# Screen_PCB_250214.net
KiCad netlist of a schematic drawn in Altium Designer
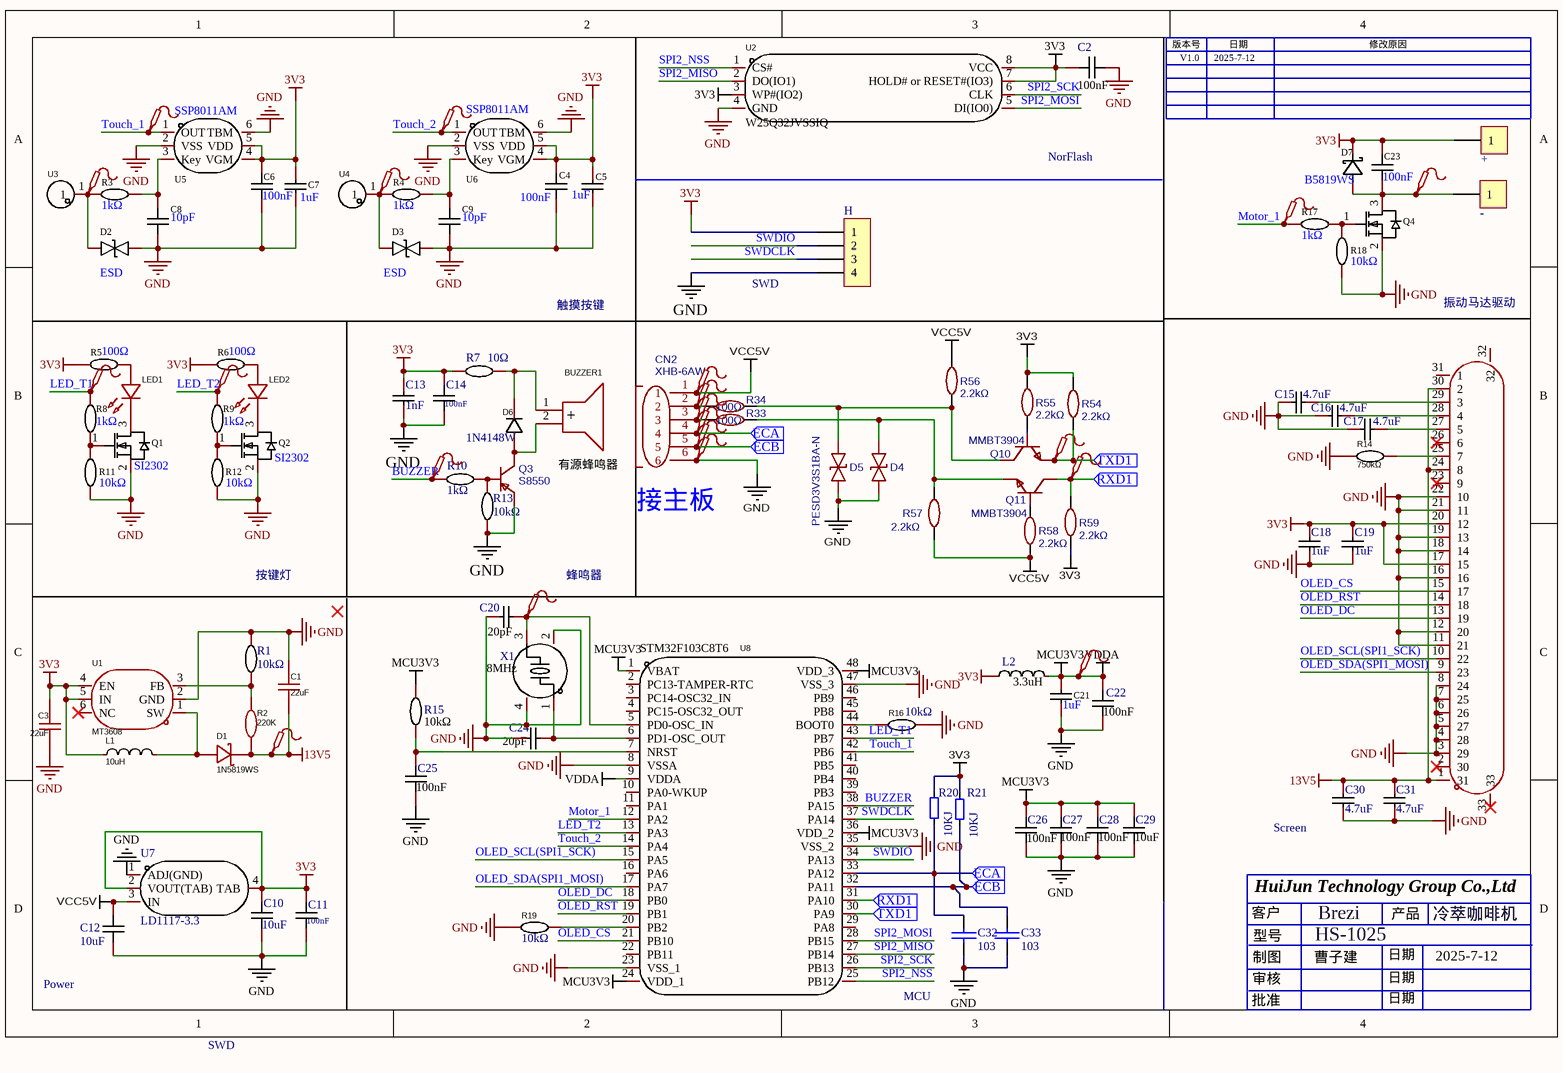
[diagram p0: Screen_PCB_250214.SchDoc]

(export (version "E")
  (design (tool "Eeschema 10.0.6"))
  (components
    (comp (ref "BUZZER1")
      (value "3kHz")
      (footprint "BUZ-TH_BD9.0-P5.00-D0.6-FD")
      (fields (field (name "MANUFACTURER") "华能") (field (name "MANUFACTURER PART") "HNB09A03"))
      (libsource (lib "PCB_Project") (part "HNB09A03"))
    )
    (comp (ref "C1")
      (value "22uF")
      (footprint "C0603")
      (fields
        (field (name "MANUFACTURER") "Chinocera(华瓷)")
        (field (name "MANUFACTURER PART") "HGC0603R5226M100NTHJ")
        (field (name "TOLERANCE") "±20%")
      )
      (libsource (lib "PCB_Project") (part "HGC0603R5226M100NTHJ"))
    )
    (comp (ref "C2")
      (value "CL10B104KB8NNNC")
      (footprint "C0603")
      (fields (field (name "SYMBOL") "100nF") (field (name "MANUFACTURER") "SAMSUNG(三星)"))
      (libsource (lib "altium-import") (part "root_2_CL10B104KB8NNNC_"))
    )
    (comp (ref "C3")
      (value "22uF")
      (footprint "C0603")
      (fields
        (field (name "MANUFACTURER") "Chinocera(华瓷)")
        (field (name "MANUFACTURER PART") "HGC0603R5226M100NTHJ")
        (field (name "TOLERANCE") "±20%")
      )
      (libsource (lib "PCB_Project") (part "HGC0603R5226M100NTHJ"))
    )
    (comp (ref "C4")
      (value "CL10B104KB8NNNC")
      (footprint "C0603")
      (fields (field (name "SYMBOL") "100nF") (field (name "MANUFACTURER") "SAMSUNG(三星)"))
      (libsource (lib "altium-import") (part "root_1_CL10B104KB8NNNC_"))
    )
    (comp (ref "C5")
      (value "0603B105K250NT")
      (footprint "C0603")
      (fields
        (field (name "MANUFACTURER") "FH(风华)")
        (field (name "TOLERANCE") "±10%")
        (field (name "NAME") "1uF")
      )
      (libsource (lib "PCB_Project") (part "0603B105K250NT"))
    )
    (comp (ref "C6")
      (value "CL10B104KB8NNNC")
      (footprint "C0603")
      (fields (field (name "SYMBOL") "100nF") (field (name "MANUFACTURER") "SAMSUNG(三星)"))
      (libsource (lib "altium-import") (part "root_1_CL10B104KB8NNNC_"))
    )
    (comp (ref "C7")
      (value "0603B105K250NT")
      (footprint "C0603")
      (fields
        (field (name "MANUFACTURER") "FH(风华)")
        (field (name "TOLERANCE") "±10%")
        (field (name "NAME") "1uF")
      )
      (libsource (lib "PCB_Project") (part "0603B105K250NT"))
    )
    (comp (ref "C8")
      (value "10pF")
      (footprint "C0603")
      (fields
        (field (name "MANUFACTURER") "FH(风华)")
        (field (name "MANUFACTURER PART") "0603CG100J500NT")
        (field (name "TOLERANCE") "±5%")
      )
      (libsource (lib "PCB_Project") (part "0603CG100J500NT"))
    )
    (comp (ref "C9")
      (value "10pF")
      (footprint "C0603")
      (fields
        (field (name "MANUFACTURER") "FH(风华)")
        (field (name "MANUFACTURER PART") "0603CG100J500NT")
        (field (name "TOLERANCE") "±5%")
      )
      (libsource (lib "PCB_Project") (part "0603CG100J500NT"))
    )
    (comp (ref "C10")
      (value "CL21A226MAQNNNE_C45783")
      (footprint "C0805")
      (fields
        (field (name "NAME") "10uF")
        (field (name "MANUFACTURER") "SAMSUNG(三星)")
        (field (name "MANUFACTURER PART") "CL21A226MAQNNNE")
        (field (name "TOLERANCE") "±20%")
      )
      (libsource (lib "altium-import") (part "root_1_CL21A226MAQNNNE_C45783_"))
    )
    (comp (ref "C11")
      (value "CL10B104KB8NNNC")
      (footprint "C0603")
      (fields (field (name "SYMBOL") "100nF") (field (name "MANUFACTURER") "SAMSUNG(三星)"))
      (libsource (lib "altium-import") (part "root_3_CL10B104KB8NNNC_"))
    )
    (comp (ref "C12")
      (value "CL21A226MAQNNNE_C45783")
      (footprint "C0805")
      (fields
        (field (name "NAME") "10uF")
        (field (name "MANUFACTURER") "SAMSUNG(三星)")
        (field (name "MANUFACTURER PART") "CL21A226MAQNNNE")
        (field (name "TOLERANCE") "±20%")
      )
      (libsource (lib "altium-import") (part "root_1_CL21A226MAQNNNE_C45783_"))
    )
    (comp (ref "C13")
      (value "CC0603KRX7R9BB102")
      (footprint "C0603")
      (fields
        (field (name "NAME") "1nF")
        (field (name "MANUFACTURER") "YAGEO(国巨)")
        (field (name "TOLERANCE") "±10%")
      )
      (libsource (lib "PCB_Project") (part "CC0603KRX7R9BB102"))
    )
    (comp (ref "C14")
      (value "CL10B104KB8NNNC")
      (footprint "C0603")
      (fields (field (name "SYMBOL") "100nF") (field (name "MANUFACTURER") "SAMSUNG(三星)"))
      (libsource (lib "altium-import") (part "root_3_CL10B104KB8NNNC_"))
    )
    (comp (ref "C15")
      (value "CL21B475KAFNNNE")
      (footprint "C0805")
      (fields
        (field (name "NAME") "4.7uF")
        (field (name "MANUFACTURER") "SAMSUNG(三星)")
        (field (name "TOLERANCE") "±10%")
      )
      (libsource (lib "PCB_Project") (part "CL21B475KAFNNNE"))
    )
    (comp (ref "C16")
      (value "CL21B475KAFNNNE")
      (footprint "C0805")
      (fields
        (field (name "NAME") "4.7uF")
        (field (name "MANUFACTURER") "SAMSUNG(三星)")
        (field (name "TOLERANCE") "±10%")
      )
      (libsource (lib "PCB_Project") (part "CL21B475KAFNNNE"))
    )
    (comp (ref "C17")
      (value "CL21B475KAFNNNE")
      (footprint "C0805")
      (fields
        (field (name "NAME") "4.7uF")
        (field (name "MANUFACTURER") "SAMSUNG(三星)")
        (field (name "TOLERANCE") "±10%")
      )
      (libsource (lib "PCB_Project") (part "CL21B475KAFNNNE"))
    )
    (comp (ref "C18")
      (value "0603B105K250NT")
      (footprint "C0603")
      (fields
        (field (name "MANUFACTURER") "FH(风华)")
        (field (name "TOLERANCE") "±10%")
        (field (name "NAME") "1uF")
      )
      (libsource (lib "PCB_Project") (part "0603B105K250NT"))
    )
    (comp (ref "C19")
      (value "0603B105K250NT")
      (footprint "C0603")
      (fields
        (field (name "MANUFACTURER") "FH(风华)")
        (field (name "TOLERANCE") "±10%")
        (field (name "NAME") "1uF")
      )
      (libsource (lib "PCB_Project") (part "0603B105K250NT"))
    )
    (comp (ref "C20")
      (value "CC0603JRNPO9BN200")
      (footprint "C0603")
      (fields
        (field (name "NAME") "20pF")
        (field (name "MANUFACTURER") "YAGEO(国巨)")
        (field (name "TOLERANCE") "±5%")
      )
      (libsource (lib "altium-import") (part "root_0_CC0603JRNPO9BN200_"))
    )
    (comp (ref "C21")
      (value "0603B105K250NT")
      (footprint "C0603")
      (fields
        (field (name "MANUFACTURER") "FH(风华)")
        (field (name "TOLERANCE") "±10%")
        (field (name "NAME") "1uF")
      )
      (libsource (lib "PCB_Project") (part "0603B105K250NT"))
    )
    (comp (ref "C22")
      (value "CL10B104KB8NNNC")
      (footprint "C0603")
      (fields (field (name "SYMBOL") "100nF") (field (name "MANUFACTURER") "SAMSUNG(三星)"))
      (libsource (lib "altium-import") (part "root_1_CL10B104KB8NNNC_"))
    )
    (comp (ref "C23")
      (value "CL10B104KB8NNNC")
      (footprint "C0603")
      (fields (field (name "SYMBOL") "100nF") (field (name "MANUFACTURER") "SAMSUNG(三星)"))
      (libsource (lib "PCB_Project") (part "CL10B104KB8NNNC"))
    )
    (comp (ref "C24")
      (value "CC0603JRNPO9BN200")
      (footprint "C0603")
      (fields
        (field (name "NAME") "20pF")
        (field (name "MANUFACTURER") "YAGEO(国巨)")
        (field (name "TOLERANCE") "±5%")
      )
      (libsource (lib "altium-import") (part "root_0_CC0603JRNPO9BN200_"))
    )
    (comp (ref "C25")
      (value "CL10B104KB8NNNC")
      (footprint "C0603")
      (fields (field (name "SYMBOL") "100nF") (field (name "MANUFACTURER") "SAMSUNG(三星)"))
      (libsource (lib "altium-import") (part "root_1_CL10B104KB8NNNC_"))
    )
    (comp (ref "C26")
      (value "CL10B104KB8NNNC")
      (footprint "C0603")
      (fields (field (name "SYMBOL") "100nF") (field (name "MANUFACTURER") "SAMSUNG(三星)"))
      (libsource (lib "altium-import") (part "root_1_CL10B104KB8NNNC_"))
    )
    (comp (ref "C27")
      (value "CL10B104KB8NNNC")
      (footprint "C0603")
      (fields (field (name "SYMBOL") "100nF") (field (name "MANUFACTURER") "SAMSUNG(三星)"))
      (libsource (lib "altium-import") (part "root_1_CL10B104KB8NNNC_"))
    )
    (comp (ref "C28")
      (value "CL10B104KB8NNNC")
      (footprint "C0603")
      (fields (field (name "SYMBOL") "100nF") (field (name "MANUFACTURER") "SAMSUNG(三星)"))
      (libsource (lib "altium-import") (part "root_1_CL10B104KB8NNNC_"))
    )
    (comp (ref "C29")
      (value "CL10A106KP8NNNC")
      (footprint "C0603")
      (fields
        (field (name "NAME") "10uF")
        (field (name "MANUFACTURER") "SAMSUNG(三星)")
        (field (name "TOLERANCE") "±10%")
      )
      (libsource (lib "PCB_Project") (part "CL10A106KP8NNNC"))
    )
    (comp (ref "C30")
      (value "CL21B475KAFNNNE")
      (footprint "C0805")
      (fields
        (field (name "NAME") "4.7uF")
        (field (name "MANUFACTURER") "SAMSUNG(三星)")
        (field (name "TOLERANCE") "±10%")
      )
      (libsource (lib "PCB_Project") (part "CL21B475KAFNNNE"))
    )
    (comp (ref "C31")
      (value "CL21B475KAFNNNE")
      (footprint "C0805")
      (fields
        (field (name "NAME") "4.7uF")
        (field (name "MANUFACTURER") "SAMSUNG(三星)")
        (field (name "TOLERANCE") "±10%")
      )
      (libsource (lib "PCB_Project") (part "CL21B475KAFNNNE"))
    )
    (comp (ref "C32")
      (value "103")
      (footprint "C0603")
      (description "Capacitor")
      (libsource (lib "HJ") (part "CAP"))
    )
    (comp (ref "C33")
      (value "103")
      (footprint "C0603")
      (description "Capacitor")
      (libsource (lib "HJ") (part "CAP"))
    )
    (comp (ref "CN2")
      (value "XHB-6AW")
      (footprint "CONN-SMD_6P-P1.25_HC-1.25-6PLT")
      (fields (field (name "MANUFACTURER") "BOOMELE(博穆精密)"))
      (libsource (lib "altium-import") (part "root_0_XHB-6AW_"))
    )
    (comp (ref "D1")
      (value "1N5819WS")
      (footprint "SOD-323_L1.8-W1.3-LS2.5-RD")
      (fields (field (name "MANUFACTURER") "Hottech(合科泰)"))
      (libsource (lib "PCB_Project") (part "1N5819WS_C191023"))
    )
    (comp (ref "D2")
      (value "BESDU0603-14")
      (footprint "D0603-BI")
      (fields (field (name "MANUFACTURER") "BORN(伯恩半导体)") (field (name "TYPE") "ESD"))
      (libsource (lib "PCB_Project") (part "BESDU0603-14"))
    )
    (comp (ref "D3")
      (value "BESDU0603-14")
      (footprint "D0603-BI")
      (fields (field (name "MANUFACTURER") "BORN(伯恩半导体)") (field (name "TYPE") "ESD"))
      (libsource (lib "PCB_Project") (part "BESDU0603-14"))
    )
    (comp (ref "D4")
      (value "PESD3V3S1BA-N")
      (footprint "SOD-523_L1.2-W0.8-LS1.6-BI")
      (fields (field (name "MANUFACTURER") "BORN(伯恩半导体)") (field (name "CONTRIBUTOR") "LCSC"))
      (libsource (lib "altium-import") (part "root_1_PESD3V3S1BA-N_"))
    )
    (comp (ref "D5")
      (value "PESD3V3S1BA-N")
      (footprint "SOD-523_L1.2-W0.8-LS1.6-BI")
      (fields (field (name "MANUFACTURER") "BORN(伯恩半导体)") (field (name "CONTRIBUTOR") "LCSC"))
      (libsource (lib "altium-import") (part "root_1_PESD3V3S1BA-N_"))
    )
    (comp (ref "D6")
      (value "1N4148W")
      (footprint "SOD-123_L2.8-W1.8-LS3.7-RD")
      (fields (field (name "MANUFACTURER") "CJ(江苏长电/长晶)"))
      (libsource (lib "PCB_Project") (part "1N4148W_C2099"))
    )
    (comp (ref "D7")
      (value "B5819WS")
      (footprint "SOD-323_L1.7-W1.3-LS2.5-FD")
      (fields (field (name "MANUFACTURER") "宏迦橙"))
      (libsource (lib "PCB_Project") (part "B5819WS_C7420331"))
    )
    (comp (ref "FPC1")
      (value "0.3K-HX-31PWB")
      (footprint "FPC-SMD_31P-P0.30_HDGC_0.3K-HX-31PWB")
      (fields (field (name "MANUFACTURER") "HDGC(华德共创)"))
      (libsource (lib "PCB_Project") (part "0.3K-HX-31PWB"))
    )
    (comp (ref "H")
      (value "CON4")
      (footprint "SIP4-2.54")
      (description "Connector")
      (libsource (lib "HJ") (part "CON4"))
    )
    (comp (ref "L1")
      (value "10uH")
      (footprint "IND-SMD_L4.0-W4.0")
      (fields
        (field (name "MANUFACTURER") "YJYCOIN(益嘉源)")
        (field (name "MANUFACTURER PART") "YNR4030-100M")
        (field (name "TOLERANCE") "±20%")
      )
      (libsource (lib "PCB_Project") (part "YNR4030-100M"))
    )
    (comp (ref "L2")
      (value "MLF1608A3R3JT000")
      (footprint "L0603")
      (fields
        (field (name "NAME") "3.3uH")
        (field (name "MANUFACTURER") "TDK")
        (field (name "TOLERANCE") "±5%")
      )
      (libsource (lib "altium-import") (part "root_0_MLF1608A3R3JT000_"))
    )
    (comp (ref "LED1")
      (value "67-21S/KK7C-H507034Z15/DT(GC)")
      (footprint "LED-SMD_L3.5-W2.8-FD-2835_WHITE")
      (fields (field (name "MANUFACTURER") "EVERLIGHT(亿光)"))
      (libsource (lib "PCB_Project") (part "67-21S/KK7C-H507034Z15/DT(GC)"))
    )
    (comp (ref "LED2")
      (value "67-21S/KK7C-H507034Z15/DT(GC)")
      (footprint "LED-SMD_L3.5-W2.8-FD-2835_WHITE")
      (fields (field (name "MANUFACTURER") "EVERLIGHT(亿光)"))
      (libsource (lib "PCB_Project") (part "67-21S/KK7C-H507034Z15/DT(GC)"))
    )
    (comp (ref "Q1")
      (value "SI2302")
      (footprint "SOT-23_L2.9-W1.3-P1.90-LS2.4-BR")
      (fields (field (name "MANUFACTURER") "GOODWORK(固得沃克)"))
      (libsource (lib "PCB_Project") (part "SI2302_C2938373"))
    )
    (comp (ref "Q2")
      (value "SI2302")
      (footprint "SOT-23_L2.9-W1.3-P1.90-LS2.4-BR")
      (fields (field (name "MANUFACTURER") "GOODWORK(固得沃克)"))
      (libsource (lib "PCB_Project") (part "SI2302_C2938373"))
    )
    (comp (ref "Q3")
      (value "S8550")
      (footprint "SOT-23_L2.9-W1.3-P0.95-LS2.4-BR")
      (fields (field (name "BOM_SUPPLIER PART") "C397181") (field (name "CONTRIBUTOR") "jiuwan321"))
      (libsource (lib "HJ") (part "PNP-S8550_C397181"))
    )
    (comp (ref "Q4")
      (value "SI2302_C2938373")
      (footprint "SOT-23_L2.9-W1.3-P1.90-LS2.4-BR")
      (fields (field (name "MANUFACTURER") "GOODWORK(固得沃克)") (field (name "MANUFACTURER PART") "SI2302"))
      (libsource (lib "PCB_Project") (part "SI2302_C2938373"))
    )
    (comp (ref "Q10")
      (value "MMBT3904")
      (footprint "SOT-23-3_L2.9-W1.3-P1.90-LS2.4-BR")
      (fields (field (name "MANUFACTURER") "CJ(江苏长电/长晶)") (field (name "CONTRIBUTOR") "立创EDA官方封装库"))
      (libsource (lib "altium-import") (part "root_3_MMBT3904_"))
    )
    (comp (ref "Q11")
      (value "MMBT3904")
      (footprint "SOT-23-3_L2.9-W1.3-P1.90-LS2.4-BR")
      (fields (field (name "MANUFACTURER") "CJ(江苏长电/长晶)") (field (name "CONTRIBUTOR") "立创EDA官方封装库"))
      (libsource (lib "altium-import") (part "root_1_MMBT3904_"))
    )
    (comp (ref "R1")
      (value "180kΩ")
      (footprint "R0603")
      (fields
        (field (name "MANUFACTURER") "UNI-ROYAL(厚声)")
        (field (name "MANUFACTURER PART") "0603WAF1002T5E")
        (field (name "NAME") "10kΩ")
      )
      (libsource (lib "PCB_Project") (part "0603WAF1002T5E"))
    )
    (comp (ref "R2")
      (value "220K")
      (footprint "R0603")
      (fields
        (field (name "MANUFACTURER") "UNI-ROYAL(厚声)")
        (field (name "MANUFACTURER PART") "0603WAF2203T5E")
        (field (name "TOLERANCE") "±1%")
      )
      (libsource (lib "PCB_Project") (part "0603WAF2203T5E"))
    )
    (comp (ref "R3")
      (value "RC0603FR-071KL")
      (footprint "R0603")
      (fields
        (field (name "NAME") "1kΩ")
        (field (name "MANUFACTURER") "YAGEO(国巨)")
        (field (name "TOLERANCE") "±1%")
      )
      (libsource (lib "PCB_Project") (part "RC0603FR-071KL"))
    )
    (comp (ref "R4")
      (value "RC0603FR-071KL")
      (footprint "R0603")
      (fields
        (field (name "NAME") "1kΩ")
        (field (name "MANUFACTURER") "YAGEO(国巨)")
        (field (name "TOLERANCE") "±1%")
      )
      (libsource (lib "PCB_Project") (part "RC0603FR-071KL"))
    )
    (comp (ref "R5")
      (value "RC0603FR-07100RL")
      (footprint "R0603")
      (fields
        (field (name "NAME") "100Ω")
        (field (name "MANUFACTURER") "YAGEO(国巨)")
        (field (name "TOLERANCE") "±1%")
      )
      (libsource (lib "PCB_Project") (part "RC0603FR-07100RL"))
    )
    (comp (ref "R6")
      (value "RC0603FR-07100RL")
      (footprint "R0603")
      (fields
        (field (name "NAME") "100Ω")
        (field (name "MANUFACTURER") "YAGEO(国巨)")
        (field (name "TOLERANCE") "±1%")
      )
      (libsource (lib "PCB_Project") (part "RC0603FR-07100RL"))
    )
    (comp (ref "R7")
      (value "0603WAF100JT5E")
      (footprint "R0603")
      (fields
        (field (name "NAME") "10Ω")
        (field (name "MANUFACTURER") "UNI-ROYAL(厚声)")
        (field (name "TOLERANCE") "±1%")
      )
      (libsource (lib "altium-import") (part "root_0_0603WAF100JT5E_"))
    )
    (comp (ref "R8")
      (value "RC0603FR-071KL")
      (footprint "R0603")
      (fields
        (field (name "NAME") "1kΩ")
        (field (name "MANUFACTURER") "YAGEO(国巨)")
        (field (name "TOLERANCE") "±1%")
      )
      (libsource (lib "PCB_Project") (part "RC0603FR-071KL"))
    )
    (comp (ref "R9")
      (value "RC0603FR-071KL")
      (footprint "R0603")
      (fields
        (field (name "NAME") "1kΩ")
        (field (name "MANUFACTURER") "YAGEO(国巨)")
        (field (name "TOLERANCE") "±1%")
      )
      (libsource (lib "PCB_Project") (part "RC0603FR-071KL"))
    )
    (comp (ref "R10")
      (value "1kΩ")
      (footprint "R0603")
      (fields
        (field (name "NAME") "1kΩ")
        (field (name "MANUFACTURER") "FH(风华)")
        (field (name "MANUFACTURER PART") "RS-03K1001FT")
      )
      (libsource (lib "altium-import") (part "root_0_RS-03K1001FT_"))
    )
    (comp (ref "R11")
      (value "10kΩ")
      (footprint "R0603")
      (fields
        (field (name "NAME") "10kΩ")
        (field (name "MANUFACTURER") "UNI-ROYAL(厚声)")
        (field (name "MANUFACTURER PART") "0603WAF1002T5E")
      )
      (libsource (lib "PCB_Project") (part "0603WAF1002T5E"))
    )
    (comp (ref "R12")
      (value "10kΩ")
      (footprint "R0603")
      (fields
        (field (name "NAME") "10kΩ")
        (field (name "MANUFACTURER") "UNI-ROYAL(厚声)")
        (field (name "MANUFACTURER PART") "0603WAF1002T5E")
      )
      (libsource (lib "PCB_Project") (part "0603WAF1002T5E"))
    )
    (comp (ref "R13")
      (value "10kΩ")
      (footprint "R0603")
      (fields
        (field (name "NAME") "10kΩ")
        (field (name "MANUFACTURER") "UNI-ROYAL(厚声)")
        (field (name "MANUFACTURER PART") "0603WAF1002T5E")
      )
      (libsource (lib "altium-import") (part "root_3_0603WAF1002T5E_"))
    )
    (comp (ref "R14")
      (value "750kΩ")
      (footprint "R0603")
      (fields
        (field (name "MANUFACTURER") "UNI-ROYAL(厚声)")
        (field (name "MANUFACTURER PART") "0603WAF7503T5E")
        (field (name "TOLERANCE") "±1%")
      )
      (libsource (lib "PCB_Project") (part "0603WAF7503T5E"))
    )
    (comp (ref "R15")
      (value "10kΩ")
      (footprint "R0603")
      (fields
        (field (name "NAME") "10kΩ")
        (field (name "MANUFACTURER") "UNI-ROYAL(厚声)")
        (field (name "MANUFACTURER PART") "0603WAF1002T5E")
      )
      (libsource (lib "altium-import") (part "root_3_0603WAF1002T5E_"))
    )
    (comp (ref "R16")
      (value "10kΩ")
      (footprint "R0603")
      (fields
        (field (name "MANUFACTURER") "UNI-ROYAL(厚声)")
        (field (name "MANUFACTURER PART") "0603WAF1002T5E")
        (field (name "TOLERANCE") "±1%")
      )
      (libsource (lib "PCB_Project") (part "0603WAF1002T5E_1"))
    )
    (comp (ref "R17")
      (value "RC0603FR-071KL")
      (footprint "R0603")
      (fields
        (field (name "NAME") "1kΩ")
        (field (name "MANUFACTURER") "YAGEO(国巨)")
        (field (name "TOLERANCE") "±1%")
      )
      (libsource (lib "PCB_Project") (part "RC0603FR-071KL"))
    )
    (comp (ref "R18")
      (value "10kΩ")
      (footprint "R0603")
      (fields
        (field (name "NAME") "10kΩ")
        (field (name "MANUFACTURER") "UNI-ROYAL(厚声)")
        (field (name "MANUFACTURER PART") "0603WAF1002T5E")
      )
      (libsource (lib "PCB_Project") (part "0603WAF1002T5E"))
    )
    (comp (ref "R19")
      (value "10kΩ")
      (footprint "R0603")
      (fields
        (field (name "MANUFACTURER") "UNI-ROYAL(厚声)")
        (field (name "MANUFACTURER PART") "0603WAF1002T5E")
        (field (name "TOLERANCE") "±1%")
      )
      (libsource (lib "PCB_Project") (part "0603WAF1002T5E_1"))
    )
    (comp (ref "R20") (value "10KJ") (footprint "R0603") (libsource (lib "HJ") (part "RES-SMD")))
    (comp (ref "R21") (value "10KJ") (footprint "R0603") (libsource (lib "HJ") (part "RES-SMD")))
    (comp (ref "R33")
      (value "100Ω")
      (footprint "R0603")
      (fields
        (field (name "MANUFACTURER") "UNI-ROYAL(厚声)")
        (field (name "MANUFACTURER PART") "0603WAF1000T5E")
      )
      (libsource (lib "altium-import") (part "root_0_100Ω_"))
    )
    (comp (ref "R34")
      (value "100Ω")
      (footprint "R0603")
      (fields
        (field (name "MANUFACTURER") "UNI-ROYAL(厚声)")
        (field (name "MANUFACTURER PART") "0603WAF1000T5E")
      )
      (libsource (lib "altium-import") (part "root_0_100Ω_"))
    )
    (comp (ref "R54")
      (value "2.2kΩ")
      (footprint "R0603")
      (fields
        (field (name "MANUFACTURER") "UNI-ROYAL(厚声)")
        (field (name "MANUFACTURER PART") "0603WAF2201T5E")
      )
      (libsource (lib "altium-import") (part "root_1_2.2kΩ_"))
    )
    (comp (ref "R55")
      (value "2.2kΩ")
      (footprint "R0603")
      (fields
        (field (name "MANUFACTURER") "UNI-ROYAL(厚声)")
        (field (name "MANUFACTURER PART") "0603WAF2201T5E")
      )
      (libsource (lib "altium-import") (part "root_1_2.2kΩ_"))
    )
    (comp (ref "R56")
      (value "2.2kΩ")
      (footprint "R0603")
      (fields
        (field (name "MANUFACTURER") "UNI-ROYAL(厚声)")
        (field (name "MANUFACTURER PART") "0603WAF2201T5E")
      )
      (libsource (lib "altium-import") (part "root_1_2.2kΩ_"))
    )
    (comp (ref "R57")
      (value "2.2kΩ")
      (footprint "R0603")
      (fields
        (field (name "MANUFACTURER") "UNI-ROYAL(厚声)")
        (field (name "MANUFACTURER PART") "0603WAF2201T5E")
      )
      (libsource (lib "altium-import") (part "root_1_2.2kΩ_"))
    )
    (comp (ref "R58")
      (value "2.2kΩ")
      (footprint "R0603")
      (fields
        (field (name "MANUFACTURER") "UNI-ROYAL(厚声)")
        (field (name "MANUFACTURER PART") "0603WAF2201T5E")
      )
      (libsource (lib "altium-import") (part "root_1_2.2kΩ_"))
    )
    (comp (ref "R59")
      (value "2.2kΩ")
      (footprint "R0603")
      (fields
        (field (name "MANUFACTURER") "UNI-ROYAL(厚声)")
        (field (name "MANUFACTURER PART") "0603WAF2201T5E")
      )
      (libsource (lib "altium-import") (part "root_1_2.2kΩ_"))
    )
    (comp (ref "T1")
      (value "+")
      (footprint "1.5MM测试点")
      (description "Connector")
      (libsource (lib "HJ") (part "CON1"))
    )
    (comp (ref "T2")
      (value "-")
      (footprint "1.5MM测试点")
      (description "Connector")
      (libsource (lib "HJ") (part "CON1"))
    )
    (comp (ref "TP1")
      (value "Test-Point")
      (footprint "Test-Point-0.5mm")
      (description "Test Point 测试点")
      (libsource (lib "HJ") (part "Test-Point"))
    )
    (comp (ref "TP2")
      (value "Test-Point")
      (footprint "Test-Point-0.5mm")
      (description "Test Point 测试点")
      (libsource (lib "HJ") (part "Test-Point"))
    )
    (comp (ref "TP3")
      (value "Test-Point")
      (footprint "Test-Point-0.5mm")
      (description "Test Point 测试点")
      (libsource (lib "HJ") (part "Test-Point"))
    )
    (comp (ref "TP4")
      (value "Test-Point")
      (footprint "Test-Point-0.5mm")
      (description "Test Point 测试点")
      (libsource (lib "HJ") (part "Test-Point"))
    )
    (comp (ref "TP5")
      (value "Test-Point")
      (footprint "Test-Point-0.5mm")
      (description "Test Point 测试点")
      (libsource (lib "HJ") (part "Test-Point"))
    )
    (comp (ref "TP6")
      (value "Test-Point")
      (footprint "Test-Point-0.5mm")
      (description "Test Point 测试点")
      (libsource (lib "HJ") (part "Test-Point"))
    )
    (comp (ref "TP7")
      (value "Test-Point")
      (footprint "Test-Point-0.5mm")
      (description "Test Point 测试点")
      (libsource (lib "HJ") (part "Test-Point"))
    )
    (comp (ref "TP8")
      (value "Test-Point")
      (footprint "Test-Point-0.5mm")
      (description "Test Point 测试点")
      (libsource (lib "HJ") (part "Test-Point"))
    )
    (comp (ref "TP9")
      (value "Test-Point")
      (footprint "Test-Point-0.5mm")
      (description "Test Point 测试点")
      (libsource (lib "HJ") (part "Test-Point"))
    )
    (comp (ref "TP10")
      (value "Test-Point")
      (footprint "Test-Point-0.5mm")
      (description "Test Point 测试点")
      (libsource (lib "HJ") (part "Test-Point"))
    )
    (comp (ref "TP11")
      (value "Test-Point")
      (footprint "Test-Point-0.5mm")
      (description "Test Point 测试点")
      (libsource (lib "HJ") (part "Test-Point"))
    )
    (comp (ref "TP12")
      (value "Test-Point")
      (footprint "Test-Point-0.5mm")
      (description "Test Point 测试点")
      (libsource (lib "HJ") (part "Test-Point"))
    )
    (comp (ref "TP13")
      (value "Test-Point")
      (footprint "Test-Point-0.5mm")
      (description "Test Point 测试点")
      (libsource (lib "HJ") (part "Test-Point"))
    )
    (comp (ref "TP15")
      (value "Test-Point")
      (footprint "Test-Point-0.5mm")
      (description "Test Point 测试点")
      (libsource (lib "HJ") (part "Test-Point"))
    )
    (comp (ref "TP16")
      (value "Test-Point")
      (footprint "Test-Point-0.5mm")
      (description "Test Point 测试点")
      (libsource (lib "HJ") (part "Test-Point"))
    )
    (comp (ref "TP17")
      (value "Test-Point")
      (footprint "Test-Point-0.5mm")
      (description "Test Point 测试点")
      (libsource (lib "HJ") (part "Test-Point"))
    )
    (comp (ref "TP18")
      (value "Test-Point")
      (footprint "Test-Point-0.5mm")
      (description "Test Point 测试点")
      (libsource (lib "HJ") (part "Test-Point"))
    )
    (comp (ref "TP19")
      (value "Test-Point")
      (footprint "Test-Point-0.5mm")
      (description "Test Point 测试点")
      (libsource (lib "HJ") (part "Test-Point"))
    )
    (comp (ref "TP20")
      (value "Test-Point")
      (footprint "Test-Point-0.5mm")
      (description "Test Point 测试点")
      (libsource (lib "HJ") (part "Test-Point"))
    )
    (comp (ref "TP21")
      (value "Test-Point")
      (footprint "Test-Point-0.5mm")
      (description "Test Point 测试点")
      (libsource (lib "HJ") (part "Test-Point"))
    )
    (comp (ref "U1")
      (value "MT3608")
      (footprint "SOT-23-6_L2.9-W1.6-P0.95-LS2.8-BL")
      (fields (field (name "MANUFACTURER") "西安航天民芯"))
      (libsource (lib "PCB_Project") (part "MT3608"))
    )
    (comp (ref "U2")
      (value "W25Q32JVSSIQ")
      (footprint "SOIC-8_L5.3-W5.3-P1.27-LS8.0-BL")
      (fields (field (name "MANUFACTURER") "WINBOND(华邦)"))
      (libsource (lib "PCB_Project") (part "W25Q32JVSSIQ"))
    )
    (comp (ref "U3")
      (value "F10-8-7-0.4")
      (footprint "F6.5-10-4.5-0.5Z")
      (fields (field (name "MANUFACTURER") "Sam&wing(芯网)"))
      (libsource (lib "PCB_Project") (part "F6.5-10-4.6-0.5Z"))
    )
    (comp (ref "U4")
      (value "F10-8-7-0.4")
      (footprint "F6.5-10-4.5-0.5Z")
      (fields (field (name "MANUFACTURER") "Sam&wing(芯网)"))
      (libsource (lib "PCB_Project") (part "F6.5-10-4.6-0.5Z"))
    )
    (comp (ref "U5")
      (value "SSP8011AM")
      (footprint "SOT-23-6_L2.9-W1.7-P0.95-LS2.8-BL")
      (fields (field (name "MANUFACTURER") "Siproin(上海矽朋)"))
      (libsource (lib "PCB_Project") (part "SSP8011AM"))
    )
    (comp (ref "U6")
      (value "SSP8011AM")
      (footprint "SOT-23-6_L2.9-W1.7-P0.95-LS2.8-BL")
      (fields (field (name "MANUFACTURER") "Siproin(上海矽朋)"))
      (libsource (lib "PCB_Project") (part "SSP8011AM"))
    )
    (comp (ref "U7")
      (value "LD1117-3.3")
      (footprint "SOT-223_L6.7-W3.5-P2.30-BR")
      (fields (field (name "NAME") "LD1117-3.3") (field (name "MANUFACTURER") "UMW(广东友台半导体)"))
      (libsource (lib "altium-import") (part "root_0_LD1117-3.3_"))
    )
    (comp (ref "U8")
      (value "STM32F103C8T6")
      (footprint "LQFP-48_L7.0-W7.0-P0.50-LS9.0-BL")
      (fields (field (name "MANUFACTURER") "ST(意法半导体)"))
      (libsource (lib "PCB_Project") (part "STM32F103C8T6"))
    )
    (comp (ref "X1")
      (value "X32258MSB4SI")
      (footprint "CRYSTAL-SMD_4P-L3.2-W2.5-BL")
      (fields (field (name "NAME") "8MHz") (field (name "MANUFACTURER") "YXC(扬兴晶振)"))
      (libsource (lib "altium-import") (part "root_1_X32258MSB4SI_"))
    )
  )
  (nets
    (net (code "1") (name "/BUZZER") (class "Default")
      (node (ref "R10") (pin "1") (pinfunction "1_1") (pintype "passive"))
      (node (ref "TP11") (pin "1") (pinfunction "1_1") (pintype "passive"))
      (node (ref "U8") (pin "38") (pinfunction "PA15_38") (pintype "passive"))
    )
    (net (code "2") (name "/ECA") (class "Default")
      (node (ref "C32") (pin "1") (pinfunction "1_1") (pintype "passive"))
      (node (ref "CN2") (pin "4") (pinfunction "4_4") (pintype "passive"))
      (node (ref "R20") (pin "2") (pinfunction "2_2") (pintype "passive"))
      (node (ref "TP4") (pin "1") (pinfunction "1_1") (pintype "passive"))
      (node (ref "U8") (pin "33") (pinfunction "PA12_33") (pintype "passive"))
    )
    (net (code "3") (name "/ECB") (class "Default")
      (node (ref "C33") (pin "1") (pinfunction "1_1") (pintype "passive"))
      (node (ref "CN2") (pin "5") (pinfunction "5_5") (pintype "passive"))
      (node (ref "R21") (pin "1") (pinfunction "1_1") (pintype "passive"))
      (node (ref "TP5") (pin "1") (pinfunction "1_1") (pintype "passive"))
      (node (ref "U8") (pin "32") (pinfunction "PA11_32") (pintype "passive"))
    )
    (net (code "4") (name "/LED_T1") (class "Default")
      (node (ref "R8") (pin "2") (pinfunction "2_2") (pintype "passive"))
      (node (ref "TP13") (pin "1") (pinfunction "1_1") (pintype "passive"))
      (node (ref "U8") (pin "43") (pinfunction "PB7_43") (pintype "passive"))
    )
    (net (code "5") (name "/LED_T2") (class "Default")
      (node (ref "R9") (pin "2") (pinfunction "2_2") (pintype "passive"))
      (node (ref "TP12") (pin "1") (pinfunction "1_1") (pintype "passive"))
      (node (ref "U8") (pin "13") (pinfunction "PA3_13") (pintype "passive"))
    )
    (net (code "6") (name "/Motor_1") (class "Default")
      (node (ref "R17") (pin "1") (pinfunction "1_1") (pintype "passive"))
      (node (ref "TP16") (pin "1") (pinfunction "1_1") (pintype "passive"))
      (node (ref "U8") (pin "12") (pinfunction "PA2_12") (pintype "passive"))
    )
    (net (code "7") (name "/OLED_CS") (class "Default")
      (node (ref "FPC1") (pin "15") (pinfunction "17_15") (pintype "passive"))
      (node (ref "U8") (pin "21") (pinfunction "PB10_21") (pintype "passive"))
    )
    (net (code "8") (name "/OLED_DC") (class "Default")
      (node (ref "FPC1") (pin "13") (pinfunction "19_13") (pintype "passive"))
      (node (ref "U8") (pin "18") (pinfunction "PB0_18") (pintype "passive"))
    )
    (net (code "9") (name "/OLED_RST") (class "Default")
      (node (ref "FPC1") (pin "14") (pinfunction "18_14") (pintype "passive"))
      (node (ref "U8") (pin "19") (pinfunction "PB1_19") (pintype "passive"))
    )
    (net (code "10") (name "/OLED_SCL(SPI1_SCK)") (class "Default")
      (node (ref "FPC1") (pin "10") (pinfunction "22_10") (pintype "passive"))
      (node (ref "U8") (pin "15") (pinfunction "PA5_15") (pintype "passive"))
    )
    (net (code "11") (name "/OLED_SDA(SPI1_MOSI)") (class "Default")
      (node (ref "FPC1") (pin "9") (pinfunction "23_9") (pintype "passive"))
      (node (ref "U8") (pin "17") (pinfunction "PA7_17") (pintype "passive"))
    )
    (net (code "12") (name "/RXD1") (class "Default")
      (node (ref "Q11") (pin "3") (pinfunction "C_3") (pintype "passive"))
      (node (ref "R59") (pin "2") (pinfunction "2_2") (pintype "passive"))
      (node (ref "TP9") (pin "1") (pinfunction "1_1") (pintype "passive"))
      (node (ref "U8") (pin "31") (pinfunction "PA10_31") (pintype "passive"))
    )
    (net (code "13") (name "/SPI2_MISO") (class "Default")
      (node (ref "U2") (pin "2") (pinfunction "DO(IO1)_2") (pintype "passive"))
      (node (ref "U8") (pin "27") (pinfunction "PB14_27") (pintype "passive"))
    )
    (net (code "14") (name "/SPI2_MOSI") (class "Default")
      (node (ref "U2") (pin "5") (pinfunction "DI(IO0)_5") (pintype "passive"))
      (node (ref "U8") (pin "28") (pinfunction "PB15_28") (pintype "passive"))
    )
    (net (code "15") (name "/SPI2_NSS") (class "Default")
      (node (ref "U2") (pin "1") (pinfunction "CS#_1") (pintype "passive"))
      (node (ref "U8") (pin "25") (pinfunction "PB12_25") (pintype "passive"))
    )
    (net (code "16") (name "/SPI2_SCK") (class "Default")
      (node (ref "U2") (pin "6") (pinfunction "CLK_6") (pintype "passive"))
      (node (ref "U8") (pin "26") (pinfunction "PB13_26") (pintype "passive"))
    )
    (net (code "17") (name "/SWDCLK") (class "Default")
      (node (ref "H") (pin "3") (pinfunction "3_3") (pintype "passive"))
      (node (ref "U8") (pin "37") (pinfunction "PA14_37") (pintype "passive"))
    )
    (net (code "18") (name "/SWDIO") (class "Default")
      (node (ref "H") (pin "2") (pinfunction "2_2") (pintype "passive"))
      (node (ref "U8") (pin "34") (pinfunction "PA13_34") (pintype "passive"))
    )
    (net (code "19") (name "/TXD1") (class "Default")
      (node (ref "Q10") (pin "2") (pinfunction "E_2") (pintype "passive"))
      (node (ref "R54") (pin "1") (pinfunction "1_1") (pintype "passive"))
      (node (ref "TP8") (pin "1") (pinfunction "1_1") (pintype "passive"))
      (node (ref "U8") (pin "30") (pinfunction "PA9_30") (pintype "passive"))
    )
    (net (code "20") (name "/Touch_1") (class "Default")
      (node (ref "TP18") (pin "1") (pinfunction "1_1") (pintype "passive"))
      (node (ref "U5") (pin "1") (pinfunction "OUT_1") (pintype "passive"))
      (node (ref "U8") (pin "42") (pinfunction "PB6_42") (pintype "passive"))
    )
    (net (code "21") (name "/Touch_2") (class "Default")
      (node (ref "TP20") (pin "1") (pinfunction "1_1") (pintype "passive"))
      (node (ref "U6") (pin "1") (pinfunction "OUT_1") (pintype "passive"))
      (node (ref "U8") (pin "14") (pinfunction "PA4_14") (pintype "passive"))
    )
    (net (code "22") (name "3V3") (class "Default")
      (node (ref "C10") (pin "2") (pinfunction "2_2") (pintype "passive"))
      (node (ref "C11") (pin "1") (pinfunction "1_1") (pintype "passive"))
      (node (ref "C13") (pin "2") (pinfunction "2_2") (pintype "passive"))
      (node (ref "C14") (pin "1") (pinfunction "1_1") (pintype "passive"))
      (node (ref "C18") (pin "2") (pinfunction "2_2") (pintype "passive"))
      (node (ref "C19") (pin "2") (pinfunction "2_2") (pintype "passive"))
      (node (ref "C2") (pin "2") (pinfunction "2_2") (pintype "passive"))
      (node (ref "C23") (pin "1") (pinfunction "1_1") (pintype "passive"))
      (node (ref "C3") (pin "2") (pinfunction "2_2") (pintype "passive"))
      (node (ref "C4") (pin "2") (pinfunction "2_2") (pintype "passive"))
      (node (ref "C5") (pin "2") (pinfunction "2_2") (pintype "passive"))
      (node (ref "C6") (pin "2") (pinfunction "2_2") (pintype "passive"))
      (node (ref "C7") (pin "2") (pinfunction "2_2") (pintype "passive"))
      (node (ref "D7") (pin "2") (pinfunction "K_2") (pintype "passive"))
      (node (ref "FPC1") (pin "17") (pinfunction "15_17") (pintype "passive"))
      (node (ref "FPC1") (pin "20") (pinfunction "12_20") (pintype "passive"))
      (node (ref "H") (pin "1") (pinfunction "1_1") (pintype "passive"))
      (node (ref "L1") (pin "1") (pinfunction "1_1") (pintype "passive"))
      (node (ref "L2") (pin "1") (pinfunction "1_1") (pintype "passive"))
      (node (ref "R20") (pin "1") (pinfunction "1_1") (pintype "passive"))
      (node (ref "R21") (pin "2") (pinfunction "2_2") (pintype "passive"))
      (node (ref "R5") (pin "2") (pinfunction "2_2") (pintype "passive"))
      (node (ref "R54") (pin "2") (pinfunction "2_2") (pintype "passive"))
      (node (ref "R55") (pin "2") (pinfunction "2_2") (pintype "passive"))
      (node (ref "R59") (pin "1") (pinfunction "1_1") (pintype "passive"))
      (node (ref "R6") (pin "2") (pinfunction "2_2") (pintype "passive"))
      (node (ref "R7") (pin "1") (pinfunction "1_1") (pintype "passive"))
      (node (ref "T1") (pin "1") (pinfunction "1_1") (pintype "passive"))
      (node (ref "U1") (pin "4") (pinfunction "EN_4") (pintype "passive"))
      (node (ref "U1") (pin "5") (pinfunction "IN_5") (pintype "passive"))
      (node (ref "U2") (pin "3") (pinfunction "WP#(IO2)_3") (pintype "passive"))
      (node (ref "U2") (pin "7") (pinfunction "HOLD#_or_RESET#(IO3)_7") (pintype "passive"))
      (node (ref "U2") (pin "8") (pinfunction "VCC_8") (pintype "passive"))
      (node (ref "U5") (pin "4") (pinfunction "VGM_4") (pintype "passive"))
      (node (ref "U5") (pin "5") (pinfunction "VDD_5") (pintype "passive"))
      (node (ref "U6") (pin "4") (pinfunction "VGM_4") (pintype "passive"))
      (node (ref "U6") (pin "5") (pinfunction "VDD_5") (pintype "passive"))
      (node (ref "U7") (pin "2") (pinfunction "VOUT(TAB)_2") (pintype "passive"))
      (node (ref "U7") (pin "4") (pinfunction "TAB_4") (pintype "passive"))
    )
    (net (code "23") (name "13V5") (class "Default")
      (node (ref "C1") (pin "1") (pinfunction "1_1") (pintype "passive"))
      (node (ref "C30") (pin "2") (pinfunction "2_2") (pintype "passive"))
      (node (ref "C31") (pin "2") (pinfunction "2_2") (pintype "passive"))
      (node (ref "D1") (pin "1") (pinfunction "K_1") (pintype "passive"))
      (node (ref "FPC1") (pin "1") (pinfunction "31_1") (pintype "passive"))
      (node (ref "FPC1") (pin "24") (pinfunction "8_24") (pintype "passive"))
      (node (ref "FPC1") (pin "30") (pinfunction "2_30") (pintype "passive"))
      (node (ref "R2") (pin "1") (pinfunction "1_1") (pintype "passive"))
      (node (ref "TP21") (pin "1") (pinfunction "1_1") (pintype "passive"))
    )
    (net (code "24") (name "GND") (class "Default")
      (node (ref "C1") (pin "2") (pinfunction "2_2") (pintype "passive"))
      (node (ref "C10") (pin "1") (pinfunction "1_1") (pintype "passive"))
      (node (ref "C11") (pin "2") (pinfunction "2_2") (pintype "passive"))
      (node (ref "C12") (pin "1") (pinfunction "1_1") (pintype "passive"))
      (node (ref "C13") (pin "1") (pinfunction "1_1") (pintype "passive"))
      (node (ref "C14") (pin "2") (pinfunction "2_2") (pintype "passive"))
      (node (ref "C15") (pin "1") (pinfunction "1_1") (pintype "passive"))
      (node (ref "C16") (pin "1") (pinfunction "1_1") (pintype "passive"))
      (node (ref "C17") (pin "1") (pinfunction "1_1") (pintype "passive"))
      (node (ref "C18") (pin "1") (pinfunction "1_1") (pintype "passive"))
      (node (ref "C19") (pin "1") (pinfunction "1_1") (pintype "passive"))
      (node (ref "C2") (pin "1") (pinfunction "1_1") (pintype "passive"))
      (node (ref "C20") (pin "1") (pinfunction "1_1") (pintype "passive"))
      (node (ref "C21") (pin "1") (pinfunction "1_1") (pintype "passive"))
      (node (ref "C22") (pin "1") (pinfunction "1_1") (pintype "passive"))
      (node (ref "C24") (pin "1") (pinfunction "1_1") (pintype "passive"))
      (node (ref "C25") (pin "1") (pinfunction "1_1") (pintype "passive"))
      (node (ref "C26") (pin "1") (pinfunction "1_1") (pintype "passive"))
      (node (ref "C27") (pin "1") (pinfunction "1_1") (pintype "passive"))
      (node (ref "C28") (pin "1") (pinfunction "1_1") (pintype "passive"))
      (node (ref "C29") (pin "1") (pinfunction "1_1") (pintype "passive"))
      (node (ref "C3") (pin "1") (pinfunction "1_1") (pintype "passive"))
      (node (ref "C30") (pin "1") (pinfunction "1_1") (pintype "passive"))
      (node (ref "C31") (pin "1") (pinfunction "1_1") (pintype "passive"))
      (node (ref "C32") (pin "2") (pinfunction "2_2") (pintype "passive"))
      (node (ref "C33") (pin "2") (pinfunction "2_2") (pintype "passive"))
      (node (ref "C4") (pin "1") (pinfunction "1_1") (pintype "passive"))
      (node (ref "C5") (pin "1") (pinfunction "1_1") (pintype "passive"))
      (node (ref "C6") (pin "1") (pinfunction "1_1") (pintype "passive"))
      (node (ref "C7") (pin "1") (pinfunction "1_1") (pintype "passive"))
      (node (ref "C8") (pin "1") (pinfunction "1_1") (pintype "passive"))
      (node (ref "C9") (pin "1") (pinfunction "1_1") (pintype "passive"))
      (node (ref "CN2") (pin "6") (pinfunction "6_6") (pintype "passive"))
      (node (ref "D2") (pin "2") (pinfunction "2_2") (pintype "passive"))
      (node (ref "D3") (pin "2") (pinfunction "2_2") (pintype "passive"))
      (node (ref "D4") (pin "1") (pinfunction "1_1") (pintype "passive"))
      (node (ref "D5") (pin "1") (pinfunction "1_1") (pintype "passive"))
      (node (ref "FPC1") (pin "11") (pinfunction "21_11") (pintype "passive"))
      (node (ref "FPC1") (pin "12") (pinfunction "20_12") (pintype "passive"))
      (node (ref "FPC1") (pin "16") (pinfunction "16_16") (pintype "passive"))
      (node (ref "FPC1") (pin "18") (pinfunction "14_18") (pintype "passive"))
      (node (ref "FPC1") (pin "19") (pinfunction "13_19") (pintype "passive"))
      (node (ref "FPC1") (pin "21") (pinfunction "11_21") (pintype "passive"))
      (node (ref "FPC1") (pin "22") (pinfunction "10_22") (pintype "passive"))
      (node (ref "FPC1") (pin "3") (pinfunction "29_3") (pintype "passive"))
      (node (ref "FPC1") (pin "4") (pinfunction "28_4") (pintype "passive"))
      (node (ref "FPC1") (pin "5") (pinfunction "27_5") (pintype "passive"))
      (node (ref "FPC1") (pin "6") (pinfunction "26_6") (pintype "passive"))
      (node (ref "FPC1") (pin "7") (pinfunction "25_7") (pintype "passive"))
      (node (ref "FPC1") (pin "8") (pinfunction "24_8") (pintype "passive"))
      (node (ref "H") (pin "4") (pinfunction "4_4") (pintype "passive"))
      (node (ref "Q1") (pin "2") (pinfunction "S_2") (pintype "passive"))
      (node (ref "Q2") (pin "2") (pinfunction "S_2") (pintype "passive"))
      (node (ref "Q3") (pin "2") (pinfunction "E_2") (pintype "passive"))
      (node (ref "Q4") (pin "2") (pinfunction "S_2") (pintype "passive"))
      (node (ref "R1") (pin "2") (pinfunction "2_2") (pintype "passive"))
      (node (ref "R11") (pin "2") (pinfunction "2_2") (pintype "passive"))
      (node (ref "R12") (pin "2") (pinfunction "2_2") (pintype "passive"))
      (node (ref "R13") (pin "2") (pinfunction "2_2") (pintype "passive"))
      (node (ref "R14") (pin "1") (pinfunction "1_1") (pintype "passive"))
      (node (ref "R16") (pin "1") (pinfunction "1_1") (pintype "passive"))
      (node (ref "R18") (pin "2") (pinfunction "2_2") (pintype "passive"))
      (node (ref "R19") (pin "1") (pinfunction "1_1") (pintype "passive"))
      (node (ref "TP6") (pin "1") (pinfunction "1_1") (pintype "passive"))
      (node (ref "U1") (pin "2") (pinfunction "GND_2") (pintype "passive"))
      (node (ref "U2") (pin "4") (pinfunction "GND_4") (pintype "passive"))
      (node (ref "U5") (pin "2") (pinfunction "VSS_2") (pintype "passive"))
      (node (ref "U5") (pin "6") (pinfunction "TBM_6") (pintype "passive"))
      (node (ref "U6") (pin "2") (pinfunction "VSS_2") (pintype "passive"))
      (node (ref "U6") (pin "6") (pinfunction "TBM_6") (pintype "passive"))
      (node (ref "U7") (pin "1") (pinfunction "ADJ(GND)_1") (pintype "passive"))
      (node (ref "U8") (pin "23") (pinfunction "VSS_1_23") (pintype "passive"))
      (node (ref "U8") (pin "35") (pinfunction "VSS_2_35") (pintype "passive"))
      (node (ref "U8") (pin "47") (pinfunction "VSS_3_47") (pintype "passive"))
      (node (ref "U8") (pin "8") (pinfunction "VSSA_8") (pintype "passive"))
      (node (ref "X1") (pin "2") (pinfunction "GND_2") (pintype "passive"))
      (node (ref "X1") (pin "4") (pinfunction "GND_4") (pintype "passive"))
    )
    (net (code "25") (name "MCU3V3") (class "Default")
      (node (ref "C21") (pin "2") (pinfunction "2_2") (pintype "passive"))
      (node (ref "C22") (pin "2") (pinfunction "2_2") (pintype "passive"))
      (node (ref "C26") (pin "2") (pinfunction "2_2") (pintype "passive"))
      (node (ref "C27") (pin "2") (pinfunction "2_2") (pintype "passive"))
      (node (ref "C28") (pin "2") (pinfunction "2_2") (pintype "passive"))
      (node (ref "C29") (pin "2") (pinfunction "2_2") (pintype "passive"))
      (node (ref "L2") (pin "2") (pinfunction "2_2") (pintype "passive"))
      (node (ref "R15") (pin "1") (pinfunction "1_1") (pintype "passive"))
      (node (ref "TP7") (pin "1") (pinfunction "1_1") (pintype "passive"))
      (node (ref "U8") (pin "1") (pinfunction "VBAT_1") (pintype "passive"))
      (node (ref "U8") (pin "24") (pinfunction "VDD_1_24") (pintype "passive"))
      (node (ref "U8") (pin "36") (pinfunction "VDD_2_36") (pintype "passive"))
      (node (ref "U8") (pin "48") (pinfunction "VDD_3_48") (pintype "passive"))
      (node (ref "U8") (pin "9") (pinfunction "VDDA_9") (pintype "passive"))
    )
    (net (code "26") (name "Net-(BUZZER1-+)") (class "Default")
      (node (ref "BUZZER1") (pin "1") (pinfunction "+_1") (pintype "passive"))
      (node (ref "D6") (pin "1") (pinfunction "K_1") (pintype "passive"))
      (node (ref "R7") (pin "2") (pinfunction "2_2") (pintype "passive"))
    )
    (net (code "27") (name "Net-(BUZZER1--)") (class "Default")
      (node (ref "BUZZER1") (pin "2") (pinfunction "-_2") (pintype "passive"))
      (node (ref "D6") (pin "2") (pinfunction "A_2") (pintype "passive"))
      (node (ref "Q3") (pin "3") (pinfunction "C_3") (pintype "passive"))
    )
    (net (code "28") (name "Net-(CN2-Pad2)") (class "Default")
      (node (ref "CN2") (pin "2") (pinfunction "2_2") (pintype "passive"))
      (node (ref "R34") (pin "1") (pinfunction "1_1") (pintype "passive"))
      (node (ref "TP2") (pin "1") (pinfunction "1_1") (pintype "passive"))
    )
    (net (code "29") (name "Net-(CN2-Pad3)") (class "Default")
      (node (ref "CN2") (pin "3") (pinfunction "3_3") (pintype "passive"))
      (node (ref "R33") (pin "1") (pinfunction "1_1") (pintype "passive"))
      (node (ref "TP3") (pin "1") (pinfunction "1_1") (pintype "passive"))
    )
    (net (code "30") (name "Net-(D1-A)") (class "Default")
      (node (ref "D1") (pin "2") (pinfunction "A_2") (pintype "passive"))
      (node (ref "L1") (pin "2") (pinfunction "2_2") (pintype "passive"))
      (node (ref "U1") (pin "1") (pinfunction "SW_1") (pintype "passive"))
    )
    (net (code "31") (name "Net-(D2-Pad1)") (class "Default")
      (node (ref "D2") (pin "1") (pinfunction "1_1") (pintype "passive"))
      (node (ref "R3") (pin "1") (pinfunction "1_1") (pintype "passive"))
      (node (ref "TP17") (pin "1") (pinfunction "1_1") (pintype "passive"))
      (node (ref "U3") (pin "1") (pinfunction "1_1") (pintype "passive"))
    )
    (net (code "32") (name "Net-(D3-Pad1)") (class "Default")
      (node (ref "D3") (pin "1") (pinfunction "1_1") (pintype "passive"))
      (node (ref "R4") (pin "1") (pinfunction "1_1") (pintype "passive"))
      (node (ref "TP19") (pin "1") (pinfunction "1_1") (pintype "passive"))
      (node (ref "U4") (pin "1") (pinfunction "1_1") (pintype "passive"))
    )
    (net (code "33") (name "Net-(D7-A)") (class "Default")
      (node (ref "C23") (pin "2") (pinfunction "2_2") (pintype "passive"))
      (node (ref "D7") (pin "1") (pinfunction "A_1") (pintype "passive"))
      (node (ref "Q4") (pin "3") (pinfunction "D_3") (pintype "passive"))
      (node (ref "T2") (pin "1") (pinfunction "1_1") (pintype "passive"))
      (node (ref "TP15") (pin "1") (pinfunction "1_1") (pintype "passive"))
    )
    (net (code "34") (name "Net-(FPC1-3)") (class "Default")
      (node (ref "C15") (pin "2") (pinfunction "2_2") (pintype "passive"))
      (node (ref "FPC1") (pin "29") (pinfunction "3_29") (pintype "passive"))
    )
    (net (code "35") (name "Net-(FPC1-4)") (class "Default")
      (node (ref "C16") (pin "2") (pinfunction "2_2") (pintype "passive"))
      (node (ref "FPC1") (pin "28") (pinfunction "4_28") (pintype "passive"))
    )
    (net (code "36") (name "Net-(FPC1-5)") (class "Default")
      (node (ref "C17") (pin "2") (pinfunction "2_2") (pintype "passive"))
      (node (ref "FPC1") (pin "27") (pinfunction "5_27") (pintype "passive"))
    )
    (net (code "37") (name "Net-(FPC1-7)") (class "Default")
      (node (ref "FPC1") (pin "25") (pinfunction "7_25") (pintype "passive"))
      (node (ref "R14") (pin "2") (pinfunction "2_2") (pintype "passive"))
    )
    (net (code "38") (name "Net-(LED1-Pad2)") (class "Default")
      (node (ref "LED1") (pin "2") (pinfunction "2_2") (pintype "passive"))
      (node (ref "R5") (pin "1") (pinfunction "1_1") (pintype "passive"))
    )
    (net (code "39") (name "Net-(LED2-Pad2)") (class "Default")
      (node (ref "LED2") (pin "2") (pinfunction "2_2") (pintype "passive"))
      (node (ref "R6") (pin "1") (pinfunction "1_1") (pintype "passive"))
    )
    (net (code "40") (name "Net-(Q1-D)") (class "Default")
      (node (ref "LED1") (pin "1") (pinfunction "1_1") (pintype "passive"))
      (node (ref "Q1") (pin "3") (pinfunction "D_3") (pintype "passive"))
    )
    (net (code "41") (name "Net-(Q1-G)") (class "Default")
      (node (ref "Q1") (pin "1") (pinfunction "G_1") (pintype "passive"))
      (node (ref "R11") (pin "1") (pinfunction "1_1") (pintype "passive"))
      (node (ref "R8") (pin "1") (pinfunction "1_1") (pintype "passive"))
    )
    (net (code "42") (name "Net-(Q2-D)") (class "Default")
      (node (ref "LED2") (pin "1") (pinfunction "1_1") (pintype "passive"))
      (node (ref "Q2") (pin "3") (pinfunction "D_3") (pintype "passive"))
    )
    (net (code "43") (name "Net-(Q2-G)") (class "Default")
      (node (ref "Q2") (pin "1") (pinfunction "G_1") (pintype "passive"))
      (node (ref "R12") (pin "1") (pinfunction "1_1") (pintype "passive"))
      (node (ref "R9") (pin "1") (pinfunction "1_1") (pintype "passive"))
    )
    (net (code "44") (name "Net-(Q3-B)") (class "Default")
      (node (ref "Q3") (pin "1") (pinfunction "B_1") (pintype "passive"))
      (node (ref "R10") (pin "2") (pinfunction "2_2") (pintype "passive"))
      (node (ref "R13") (pin "1") (pinfunction "1_1") (pintype "passive"))
    )
    (net (code "45") (name "Net-(Q4-G)") (class "Default")
      (node (ref "Q4") (pin "1") (pinfunction "G_1") (pintype "passive"))
      (node (ref "R17") (pin "2") (pinfunction "2_2") (pintype "passive"))
      (node (ref "R18") (pin "1") (pinfunction "1_1") (pintype "passive"))
    )
    (net (code "46") (name "Net-(Q10-B)") (class "Default")
      (node (ref "Q10") (pin "1") (pinfunction "B_1") (pintype "passive"))
      (node (ref "R55") (pin "1") (pinfunction "1_1") (pintype "passive"))
    )
    (net (code "47") (name "Net-(Q10-C)") (class "Default")
      (node (ref "D5") (pin "2") (pinfunction "2_2") (pintype "passive"))
      (node (ref "Q10") (pin "3") (pinfunction "C_3") (pintype "passive"))
      (node (ref "R34") (pin "2") (pinfunction "2_2") (pintype "passive"))
      (node (ref "R56") (pin "1") (pinfunction "1_1") (pintype "passive"))
    )
    (net (code "48") (name "Net-(Q11-B)") (class "Default")
      (node (ref "Q11") (pin "1") (pinfunction "B_1") (pintype "passive"))
      (node (ref "R58") (pin "2") (pinfunction "2_2") (pintype "passive"))
    )
    (net (code "49") (name "Net-(Q11-E)") (class "Default")
      (node (ref "D4") (pin "2") (pinfunction "2_2") (pintype "passive"))
      (node (ref "Q11") (pin "2") (pinfunction "E_2") (pintype "passive"))
      (node (ref "R33") (pin "2") (pinfunction "2_2") (pintype "passive"))
      (node (ref "R57") (pin "2") (pinfunction "2_2") (pintype "passive"))
    )
    (net (code "50") (name "Net-(U1-FB)") (class "Default")
      (node (ref "R1") (pin "1") (pinfunction "1_1") (pintype "passive"))
      (node (ref "R2") (pin "2") (pinfunction "2_2") (pintype "passive"))
      (node (ref "U1") (pin "3") (pinfunction "FB_3") (pintype "passive"))
    )
    (net (code "51") (name "Net-(U5-Key)") (class "Default")
      (node (ref "C8") (pin "2") (pinfunction "2_2") (pintype "passive"))
      (node (ref "R3") (pin "2") (pinfunction "2_2") (pintype "passive"))
      (node (ref "U5") (pin "3") (pinfunction "Key_3") (pintype "passive"))
    )
    (net (code "52") (name "Net-(U6-Key)") (class "Default")
      (node (ref "C9") (pin "2") (pinfunction "2_2") (pintype "passive"))
      (node (ref "R4") (pin "2") (pinfunction "2_2") (pintype "passive"))
      (node (ref "U6") (pin "3") (pinfunction "Key_3") (pintype "passive"))
    )
    (net (code "53") (name "Net-(U8-BOOT0)") (class "Default")
      (node (ref "R16") (pin "2") (pinfunction "2_2") (pintype "passive"))
      (node (ref "U8") (pin "44") (pinfunction "BOOT0_44") (pintype "passive"))
    )
    (net (code "54") (name "Net-(U8-NRST)") (class "Default")
      (node (ref "C25") (pin "2") (pinfunction "2_2") (pintype "passive"))
      (node (ref "R15") (pin "2") (pinfunction "2_2") (pintype "passive"))
      (node (ref "U8") (pin "7") (pinfunction "NRST_7") (pintype "passive"))
    )
    (net (code "55") (name "Net-(U8-PB2)") (class "Default")
      (node (ref "R19") (pin "2") (pinfunction "2_2") (pintype "passive"))
      (node (ref "U8") (pin "20") (pinfunction "PB2_20") (pintype "passive"))
    )
    (net (code "56") (name "Net-(U8-PD0-OSC_IN)") (class "Default")
      (node (ref "C20") (pin "2") (pinfunction "2_2") (pintype "passive"))
      (node (ref "TP10") (pin "1") (pinfunction "1_1") (pintype "passive"))
      (node (ref "U8") (pin "5") (pinfunction "PD0-OSC_IN_5") (pintype "passive"))
      (node (ref "X1") (pin "3") (pinfunction "3_3") (pintype "passive"))
    )
    (net (code "57") (name "Net-(U8-PD1-OSC_OUT)") (class "Default")
      (node (ref "C24") (pin "2") (pinfunction "2_2") (pintype "passive"))
      (node (ref "U8") (pin "6") (pinfunction "PD1-OSC_OUT_6") (pintype "passive"))
      (node (ref "X1") (pin "1") (pinfunction "1_1") (pintype "passive"))
    )
    (net (code "58") (name "VCC5V") (class "Default")
      (node (ref "C12") (pin "2") (pinfunction "2_2") (pintype "passive"))
      (node (ref "CN2") (pin "1") (pinfunction "1_1") (pintype "passive"))
      (node (ref "R56") (pin "2") (pinfunction "2_2") (pintype "passive"))
      (node (ref "R57") (pin "1") (pinfunction "1_1") (pintype "passive"))
      (node (ref "R58") (pin "1") (pinfunction "1_1") (pintype "passive"))
      (node (ref "TP1") (pin "1") (pinfunction "1_1") (pintype "passive"))
      (node (ref "U7") (pin "3") (pinfunction "IN_3") (pintype "passive"))
    )
    (net (code "59") (name "unconnected-(FPC1-1-Pad31)") (class "Default")
      (node (ref "FPC1") (pin "31") (pinfunction "1_31") (pintype "passive"))
    )
    (net (code "60") (name "unconnected-(FPC1-6-Pad26)") (class "Default")
      (node (ref "FPC1") (pin "26") (pinfunction "6_26") (pintype "passive+no_connect"))
    )
    (net (code "61") (name "unconnected-(FPC1-9-Pad23)") (class "Default")
      (node (ref "FPC1") (pin "23") (pinfunction "9_23") (pintype "passive+no_connect"))
    )
    (net (code "62") (name "unconnected-(FPC1-30-Pad2)") (class "Default")
      (node (ref "FPC1") (pin "2") (pinfunction "30_2") (pintype "passive+no_connect"))
    )
    (net (code "63") (name "unconnected-(FPC1-Pad32)") (class "Default")
      (node (ref "FPC1") (pin "32") (pinfunction "32_32") (pintype "passive"))
    )
    (net (code "64") (name "unconnected-(FPC1-Pad33)") (class "Default")
      (node (ref "FPC1") (pin "33") (pinfunction "33_33") (pintype "passive+no_connect"))
    )
    (net (code "65") (name "unconnected-(U1-NC-Pad6)") (class "Default")
      (node (ref "U1") (pin "6") (pinfunction "NC_6") (pintype "passive+no_connect"))
    )
    (net (code "66") (name "unconnected-(U8-PA0-WKUP-Pad10)") (class "Default")
      (node (ref "U8") (pin "10") (pinfunction "PA0-WKUP_10") (pintype "passive"))
    )
    (net (code "67") (name "unconnected-(U8-PA1-Pad11)") (class "Default")
      (node (ref "U8") (pin "11") (pinfunction "PA1_11") (pintype "passive"))
    )
    (net (code "68") (name "unconnected-(U8-PA6-Pad16)") (class "Default")
      (node (ref "U8") (pin "16") (pinfunction "PA6_16") (pintype "passive"))
    )
    (net (code "69") (name "unconnected-(U8-PA8-Pad29)") (class "Default")
      (node (ref "U8") (pin "29") (pinfunction "PA8_29") (pintype "passive"))
    )
    (net (code "70") (name "unconnected-(U8-PB3-Pad39)") (class "Default")
      (node (ref "U8") (pin "39") (pinfunction "PB3_39") (pintype "passive"))
    )
    (net (code "71") (name "unconnected-(U8-PB4-Pad40)") (class "Default")
      (node (ref "U8") (pin "40") (pinfunction "PB4_40") (pintype "passive"))
    )
    (net (code "72") (name "unconnected-(U8-PB5-Pad41)") (class "Default")
      (node (ref "U8") (pin "41") (pinfunction "PB5_41") (pintype "passive"))
    )
    (net (code "73") (name "unconnected-(U8-PB8-Pad45)") (class "Default")
      (node (ref "U8") (pin "45") (pinfunction "PB8_45") (pintype "passive"))
    )
    (net (code "74") (name "unconnected-(U8-PB9-Pad46)") (class "Default")
      (node (ref "U8") (pin "46") (pinfunction "PB9_46") (pintype "passive"))
    )
    (net (code "75") (name "unconnected-(U8-PB11-Pad22)") (class "Default")
      (node (ref "U8") (pin "22") (pinfunction "PB11_22") (pintype "passive"))
    )
    (net (code "76") (name "unconnected-(U8-PC13-TAMPER-RTC-Pad2)") (class "Default")
      (node (ref "U8") (pin "2") (pinfunction "PC13-TAMPER-RTC_2") (pintype "passive"))
    )
    (net (code "77") (name "unconnected-(U8-PC14-OSC32_IN-Pad3)") (class "Default")
      (node (ref "U8") (pin "3") (pinfunction "PC14-OSC32_IN_3") (pintype "passive"))
    )
    (net (code "78") (name "unconnected-(U8-PC15-OSC32_OUT-Pad4)") (class "Default")
      (node (ref "U8") (pin "4") (pinfunction "PC15-OSC32_OUT_4") (pintype "passive"))
    )
  )
)
